# S3_-_CONNECTORS.net
KiCad netlist of a schematic drawn in Altium Designer
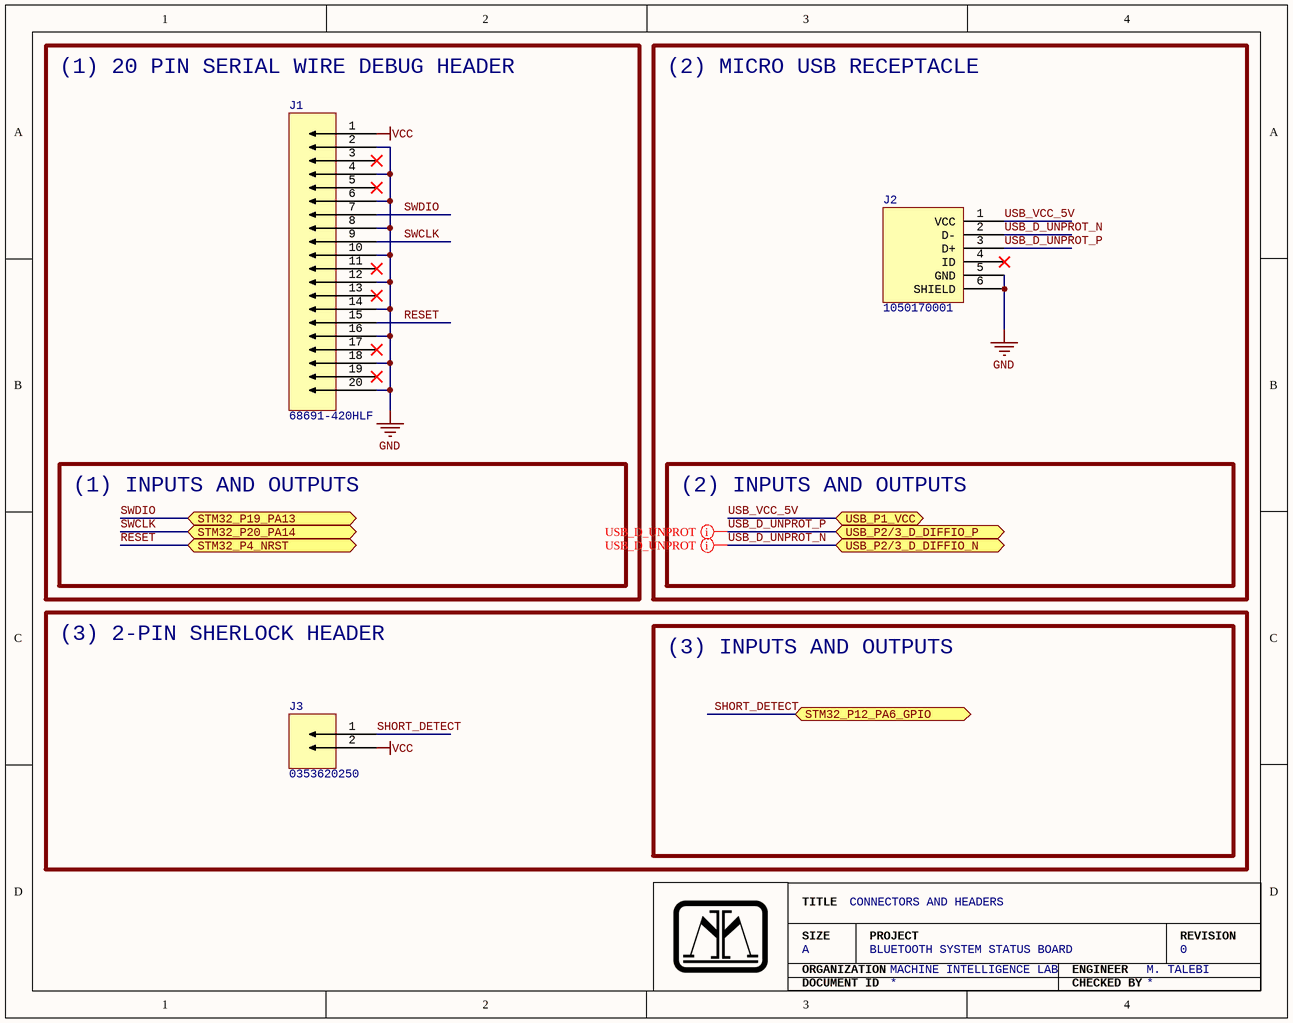
[diagram p0: S3 - CONNECTORS.SchDoc]

(export (version "E")
  (design (tool "Eeschema 10.0.6"))
  (components
    (comp (ref "J1")
      (value "68691-420HLF")
      (footprint "68691-420HLF")
      (description "CONN HEADER VERT 20POS 2.54MM")
      (libsource (lib "Master") (part "68691-420HLF"))
    )
    (comp (ref "J2")
      (value "1050170001")
      (footprint "1050170001")
      (description "CONN RCPT USB2.0 MICRO B SMD R/A")
      (libsource (lib "Master") (part "1050170001"))
    )
    (comp (ref "J3")
      (value "0353620250")
      (footprint "0353620250")
      (description "CONN HEADER VERT 2POS 2MM")
      (libsource (lib "Master") (part "0353620250"))
    )
  )
  (nets
    (net (code "1") (name "/RESET") (class "Default")
      (node (ref "J1") (pin "15") (pinfunction "48_15") (pintype "passive"))
    )
    (net (code "2") (name "/SHORT_DETECT") (class "Default")
      (node (ref "J3") (pin "1") (pinfunction "34_1") (pintype "passive"))
    )
    (net (code "3") (name "/SWCLK") (class "Default")
      (node (ref "J1") (pin "9") (pinfunction "42_9") (pintype "passive"))
    )
    (net (code "4") (name "/SWDIO") (class "Default")
      (node (ref "J1") (pin "7") (pinfunction "40_7") (pintype "passive"))
    )
    (net (code "5") (name "/USB_D_UNPROT_N") (class "Default")
      (node (ref "J2") (pin "2") (pinfunction "D-_2") (pintype "passive"))
    )
    (net (code "6") (name "/USB_D_UNPROT_P") (class "Default")
      (node (ref "J2") (pin "3") (pinfunction "D+_3") (pintype "passive"))
    )
    (net (code "7") (name "/USB_VCC_5V") (class "Default")
      (node (ref "J2") (pin "1") (pinfunction "VCC_1") (pintype "passive"))
    )
    (net (code "8") (name "GND") (class "Default")
      (node (ref "J1") (pin "10") (pinfunction "43_10") (pintype "passive"))
      (node (ref "J1") (pin "12") (pinfunction "45_12") (pintype "passive"))
      (node (ref "J1") (pin "14") (pinfunction "47_14") (pintype "passive"))
      (node (ref "J1") (pin "16") (pinfunction "49_16") (pintype "passive"))
      (node (ref "J1") (pin "18") (pinfunction "51_18") (pintype "passive"))
      (node (ref "J1") (pin "2") (pinfunction "35_2") (pintype "passive"))
      (node (ref "J1") (pin "20") (pinfunction "53_20") (pintype "passive"))
      (node (ref "J1") (pin "4") (pinfunction "37_4") (pintype "passive"))
      (node (ref "J1") (pin "6") (pinfunction "39_6") (pintype "passive"))
      (node (ref "J1") (pin "8") (pinfunction "41_8") (pintype "passive"))
      (node (ref "J2") (pin "5") (pinfunction "GND_5") (pintype "passive"))
      (node (ref "J2") (pin "6") (pinfunction "SHIELD_6") (pintype "passive"))
    )
    (net (code "9") (name "VCC") (class "Default")
      (node (ref "J1") (pin "1") (pinfunction "34_1") (pintype "passive"))
      (node (ref "J3") (pin "2") (pinfunction "35_2") (pintype "passive"))
    )
    (net (code "10") (name "unconnected-(J1-36-Pad3)") (class "Default")
      (node (ref "J1") (pin "3") (pinfunction "36_3") (pintype "passive+no_connect"))
    )
    (net (code "11") (name "unconnected-(J1-38-Pad5)") (class "Default")
      (node (ref "J1") (pin "5") (pinfunction "38_5") (pintype "passive+no_connect"))
    )
    (net (code "12") (name "unconnected-(J1-44-Pad11)") (class "Default")
      (node (ref "J1") (pin "11") (pinfunction "44_11") (pintype "passive+no_connect"))
    )
    (net (code "13") (name "unconnected-(J1-46-Pad13)") (class "Default")
      (node (ref "J1") (pin "13") (pinfunction "46_13") (pintype "passive+no_connect"))
    )
    (net (code "14") (name "unconnected-(J1-50-Pad17)") (class "Default")
      (node (ref "J1") (pin "17") (pinfunction "50_17") (pintype "passive+no_connect"))
    )
    (net (code "15") (name "unconnected-(J1-52-Pad19)") (class "Default")
      (node (ref "J1") (pin "19") (pinfunction "52_19") (pintype "passive+no_connect"))
    )
    (net (code "16") (name "unconnected-(J2-ID-Pad4)") (class "Default")
      (node (ref "J2") (pin "4") (pinfunction "ID_4") (pintype "passive+no_connect"))
    )
  )
)
